# Memory.net
KiCad netlist of a schematic drawn in Altium Designer
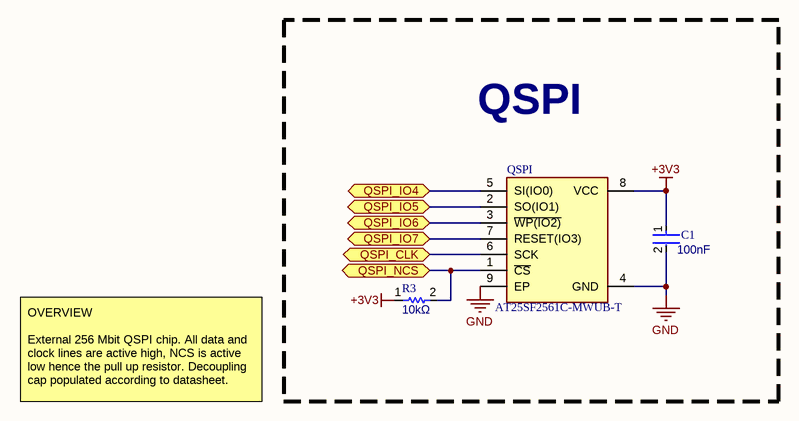
[diagram p0: Memory.SchDoc]

(export (version "E")
  (design (tool "Eeschema 10.0.6"))
  (components
    (comp (ref "C1")
      (value "100nF")
      (footprint "FP-GCM188-0_1-IPC_B")
      (description "Cap Ceramic 0.1uF 50V X8L 20% Pad SMD 0603 150C Automotive T/R")
      (fields
        (field (name "TOLERANCE") "20%")
        (field (name "Comment") "GCM188L81H104MA57D")
        (field (name "ADDED BY") "Felix")
      )
      (libsource (lib "Perth Aerospace Student Team") (part "02cd4be3c70576c341d710602a673aa"))
    )
    (comp (ref "QSPI")
      (value "AT25SF2561C-MWUB-T")
      (footprint "SON127P800X600X80-9N-D")
      (description "Integrated Circuit")
      (fields (field (name "IMPORTED BY") "Felix"))
      (libsource (lib "Perth Aerospace Student Team") (part "AT25SF2561C-MWUB-T"))
    )
    (comp (ref "R3")
      (value "10kΩ")
      (footprint "FP-CRCW0603-e3-IPC_C")
      (description "Resistor")
      (fields
        (field (name "TOLERANCE") "1%")
        (field (name "Comment") "CRCW060310K0FKED")
        (field (name "ADDED BY") "Felix")
      )
      (libsource (lib "Perth Aerospace Student Team") (part "1029c3af85768c4190bb7ad29bc67b5"))
    )
  )
  (nets
    (net (code "1") (name "+3V3") (class "Default")
      (node (ref "C1") (pin "1") (pinfunction "1_1") (pintype "passive"))
      (node (ref "QSPI") (pin "8") (pinfunction "VCC_8") (pintype "passive"))
      (node (ref "R3") (pin "1") (pinfunction "1_1") (pintype "passive"))
    )
    (net (code "2") (name "/QSPI_CLK") (class "Default")
      (node (ref "QSPI") (pin "6") (pinfunction "SCK_6") (pintype "passive"))
    )
    (net (code "3") (name "/QSPI_IO4") (class "Default")
      (node (ref "QSPI") (pin "5") (pinfunction "SI(IO0)_5") (pintype "passive"))
    )
    (net (code "4") (name "/QSPI_IO5") (class "Default")
      (node (ref "QSPI") (pin "2") (pinfunction "SO(IO1)_2") (pintype "passive"))
    )
    (net (code "5") (name "/QSPI_IO6") (class "Default")
      (node (ref "QSPI") (pin "3") (pinfunction "~{WP(IO2)}_3") (pintype "passive"))
    )
    (net (code "6") (name "/QSPI_IO7") (class "Default")
      (node (ref "QSPI") (pin "7") (pinfunction "RESET(IO3)_7") (pintype "passive"))
    )
    (net (code "7") (name "/QSPI_NCS") (class "Default")
      (node (ref "QSPI") (pin "1") (pinfunction "~{CS}_1") (pintype "passive"))
      (node (ref "R3") (pin "2") (pinfunction "2_2") (pintype "passive"))
    )
    (net (code "8") (name "GND") (class "Default")
      (node (ref "C1") (pin "2") (pinfunction "2_2") (pintype "passive"))
      (node (ref "QSPI") (pin "4") (pinfunction "GND_4") (pintype "passive"))
      (node (ref "QSPI") (pin "9") (pinfunction "EP_9") (pintype "passive"))
    )
  )
)
